# Reflow_Oven_Other_Circuits.net
KiCad netlist of a schematic drawn in EAGLE
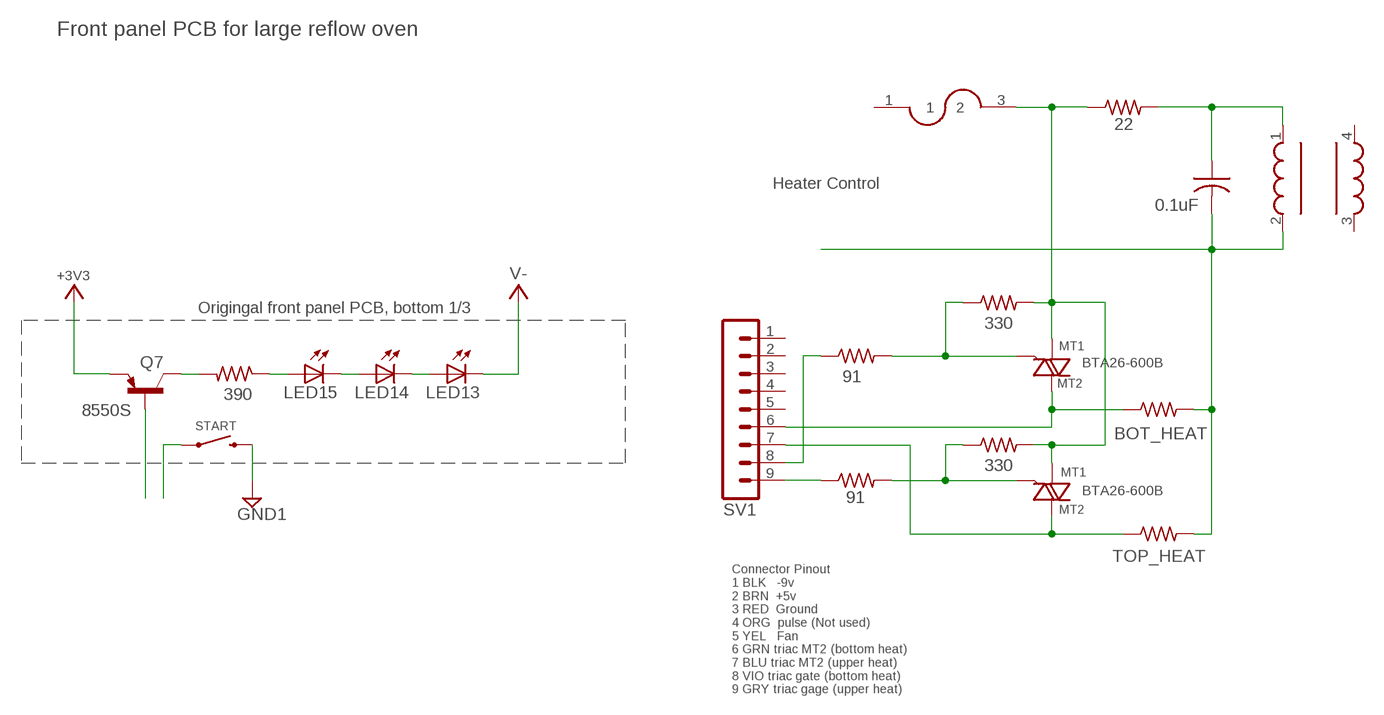
[diagram p0: schematic, sheet 1]

(export (version "E")
  (design (tool "Eeschema 10.0.6"))
  (components
    (comp (ref "BOT_HEAT")
      (value "R-US_0207/10")
      (footprint "eagle-import:0207_10")
      (libsource (lib "eagle-import") (part "R-US_0207/10"))
    )
    (comp (ref "C2")
      (value "0.1uF")
      (footprint "eagle-import:C050-030X075")
      (libsource (lib "eagle-import") (part "C-US050-030X075"))
    )
    (comp (ref "F3")
      (value "FUSEX20MM")
      (footprint "eagle-import:FUSE_5MM")
      (libsource (lib "eagle-import") (part "FUSEX20MM"))
    )
    (comp (ref "LED13")
      (value "LED5MM")
      (footprint "eagle-import:LED5MM")
      (libsource (lib "eagle-import") (part "LED5MM"))
    )
    (comp (ref "LED14")
      (value "LED5MM")
      (footprint "eagle-import:LED5MM")
      (libsource (lib "eagle-import") (part "LED5MM"))
    )
    (comp (ref "LED15")
      (value "LED5MM")
      (footprint "eagle-import:LED5MM")
      (libsource (lib "eagle-import") (part "LED5MM"))
    )
    (comp (ref "Q7")
      (value "8550S")
      (footprint "eagle-import:TO92-EBC")
      (libsource (lib "eagle-import") (part "-PNP-TO92-EBCBC327-40"))
    )
    (comp (ref "R1")
      (value "390")
      (footprint "eagle-import:0207_10")
      (libsource (lib "eagle-import") (part "R-US_0207/10"))
    )
    (comp (ref "R6")
      (value "22")
      (footprint "eagle-import:0207_10")
      (libsource (lib "eagle-import") (part "R-US_0207/10"))
    )
    (comp (ref "R7")
      (value "91")
      (footprint "eagle-import:0207_10")
      (libsource (lib "eagle-import") (part "R-US_0207/10"))
    )
    (comp (ref "R8")
      (value "91")
      (footprint "eagle-import:0207_10")
      (libsource (lib "eagle-import") (part "R-US_0207/10"))
    )
    (comp (ref "R9")
      (value "330")
      (footprint "eagle-import:0207_10")
      (libsource (lib "eagle-import") (part "R-US_0207/10"))
    )
    (comp (ref "R10")
      (value "330")
      (footprint "eagle-import:0207_10")
      (libsource (lib "eagle-import") (part "R-US_0207/10"))
    )
    (comp (ref "START")
      (value "SWITCH-MOMENTARY-2PTH")
      (footprint "eagle-import:TACTILE-PTH")
      (libsource (lib "eagle-import") (part "SWITCH-MOMENTARY-2PTH"))
    )
    (comp (ref "SV1")
      (value "MA09-1")
      (footprint "eagle-import:MA09-1")
      (libsource (lib "eagle-import") (part "MA09-1"))
    )
    (comp (ref "T1")
      (value "BTA26-600B")
      (footprint "eagle-import:TOP3L-1")
      (libsource (lib "eagle-import") (part "BTA26-H"))
    )
    (comp (ref "T2")
      (value "BTA26-600B")
      (footprint "eagle-import:TOP3L-1")
      (libsource (lib "eagle-import") (part "BTA26-H"))
    )
    (comp (ref "TOP_HEAT")
      (value "R-US_0207/10")
      (footprint "eagle-import:0207_10")
      (libsource (lib "eagle-import") (part "R-US_0207/10"))
    )
    (comp (ref "U$1")
      (value "TRANSFORMERPTH")
      (footprint "eagle-import:TRANSFORMER")
      (libsource (lib "eagle-import") (part "TRANSFORMERPTH"))
    )
  )
  (nets
    (net (code "1") (name "+3V3") (class "Default")
      (node (ref "Q7") (pin "E") (pinfunction "E_E") (pintype "passive"))
    )
    (net (code "2") (name "GND1") (class "Default")
      (node (ref "START") (pin "3") (pinfunction "2_3") (pintype "passive"))
    )
    (net (code "3") (name "Net-(BOT_HEAT-Pad1)") (class "Default")
      (node (ref "BOT_HEAT") (pin "1") (pinfunction "1_1") (pintype "passive"))
      (node (ref "SV1") (pin "6") (pinfunction "6_6") (pintype "passive"))
      (node (ref "T1") (pin "A2") (pinfunction "A2_A2") (pintype "passive"))
    )
    (net (code "4") (name "Net-(BOT_HEAT-Pad2)") (class "Default")
      (node (ref "BOT_HEAT") (pin "2") (pinfunction "2_2") (pintype "passive"))
      (node (ref "C2") (pin "2") (pinfunction "2_2") (pintype "passive"))
      (node (ref "TOP_HEAT") (pin "2") (pinfunction "2_2") (pintype "passive"))
      (node (ref "U$1") (pin "2") (pinfunction "2_2") (pintype "bidirectional"))
    )
    (net (code "5") (name "Net-(C2-Pad1)") (class "Default")
      (node (ref "C2") (pin "1") (pinfunction "1_1") (pintype "passive"))
      (node (ref "R6") (pin "2") (pinfunction "2_2") (pintype "passive"))
      (node (ref "U$1") (pin "1") (pinfunction "1_1") (pintype "bidirectional"))
    )
    (net (code "6") (name "Net-(F3-2)") (class "Default")
      (node (ref "F3") (pin "3") (pinfunction "2_3") (pintype "bidirectional"))
      (node (ref "R10") (pin "2") (pinfunction "2_2") (pintype "passive"))
      (node (ref "R6") (pin "1") (pinfunction "1_1") (pintype "passive"))
      (node (ref "R9") (pin "2") (pinfunction "2_2") (pintype "passive"))
      (node (ref "T1") (pin "A1") (pinfunction "A1_A1") (pintype "passive"))
      (node (ref "T2") (pin "A1") (pinfunction "A1_A1") (pintype "passive"))
    )
    (net (code "7") (name "Net-(LED14-C)") (class "Default")
      (node (ref "LED13") (pin "A") (pinfunction "A_A") (pintype "passive"))
      (node (ref "LED14") (pin "K") (pinfunction "C_K") (pintype "passive"))
    )
    (net (code "8") (name "Net-(LED15-C)") (class "Default")
      (node (ref "LED14") (pin "A") (pinfunction "A_A") (pintype "passive"))
      (node (ref "LED15") (pin "K") (pinfunction "C_K") (pintype "passive"))
    )
    (net (code "9") (name "Net-(LED15-PadA)") (class "Default")
      (node (ref "LED15") (pin "A") (pinfunction "A_A") (pintype "passive"))
      (node (ref "R1") (pin "1") (pinfunction "1_1") (pintype "passive"))
    )
    (net (code "10") (name "Net-(Q7-PadC)") (class "Default")
      (node (ref "Q7") (pin "C") (pinfunction "C_C") (pintype "passive"))
      (node (ref "R1") (pin "2") (pinfunction "2_2") (pintype "passive"))
    )
    (net (code "11") (name "Net-(R7-Pad1)") (class "Default")
      (node (ref "R7") (pin "1") (pinfunction "1_1") (pintype "passive"))
      (node (ref "SV1") (pin "8") (pinfunction "8_8") (pintype "passive"))
    )
    (net (code "12") (name "Net-(R7-Pad2)") (class "Default")
      (node (ref "R7") (pin "2") (pinfunction "2_2") (pintype "passive"))
      (node (ref "R9") (pin "1") (pinfunction "1_1") (pintype "passive"))
      (node (ref "T1") (pin "G") (pinfunction "G_G") (pintype "passive"))
    )
    (net (code "13") (name "Net-(R8-Pad1)") (class "Default")
      (node (ref "R8") (pin "1") (pinfunction "1_1") (pintype "passive"))
      (node (ref "SV1") (pin "9") (pinfunction "9_9") (pintype "passive"))
    )
    (net (code "14") (name "Net-(R10-Pad1)") (class "Default")
      (node (ref "R10") (pin "1") (pinfunction "1_1") (pintype "passive"))
      (node (ref "R8") (pin "2") (pinfunction "2_2") (pintype "passive"))
      (node (ref "T2") (pin "G") (pinfunction "G_G") (pintype "passive"))
    )
    (net (code "15") (name "Net-(SV1-Pad7)") (class "Default")
      (node (ref "SV1") (pin "7") (pinfunction "7_7") (pintype "passive"))
      (node (ref "T2") (pin "A2") (pinfunction "A2_A2") (pintype "passive"))
      (node (ref "TOP_HEAT") (pin "1") (pinfunction "1_1") (pintype "passive"))
    )
    (net (code "16") (name "V-") (class "Default")
      (node (ref "LED13") (pin "K") (pinfunction "C_K") (pintype "passive"))
    )
    (net (code "17") (name "unconnected-(F3-Pad1)") (class "Default")
      (node (ref "F3") (pin "1") (pinfunction "1_1") (pintype "bidirectional"))
    )
    (net (code "18") (name "unconnected-(Q7-PadB)") (class "Default")
      (node (ref "Q7") (pin "B") (pinfunction "B_B") (pintype "passive"))
    )
    (net (code "19") (name "unconnected-(START-Pad1)") (class "Default")
      (node (ref "START") (pin "1") (pinfunction "1_1") (pintype "passive"))
    )
    (net (code "20") (name "unconnected-(SV1-Pad1)") (class "Default")
      (node (ref "SV1") (pin "1") (pinfunction "1_1") (pintype "passive"))
    )
    (net (code "21") (name "unconnected-(SV1-Pad2)") (class "Default")
      (node (ref "SV1") (pin "2") (pinfunction "2_2") (pintype "passive"))
    )
    (net (code "22") (name "unconnected-(SV1-Pad3)") (class "Default")
      (node (ref "SV1") (pin "3") (pinfunction "3_3") (pintype "passive"))
    )
    (net (code "23") (name "unconnected-(SV1-Pad4)") (class "Default")
      (node (ref "SV1") (pin "4") (pinfunction "4_4") (pintype "passive"))
    )
    (net (code "24") (name "unconnected-(SV1-Pad5)") (class "Default")
      (node (ref "SV1") (pin "5") (pinfunction "5_5") (pintype "passive"))
    )
    (net (code "25") (name "unconnected-(U$1-Pad3)") (class "Default")
      (node (ref "U$1") (pin "3") (pinfunction "3_3") (pintype "bidirectional"))
    )
    (net (code "26") (name "unconnected-(U$1-Pad4)") (class "Default")
      (node (ref "U$1") (pin "4") (pinfunction "4_4") (pintype "bidirectional"))
    )
  )
)
